# Bike_Seat_Light.net
KiCad netlist of a schematic drawn in EAGLE
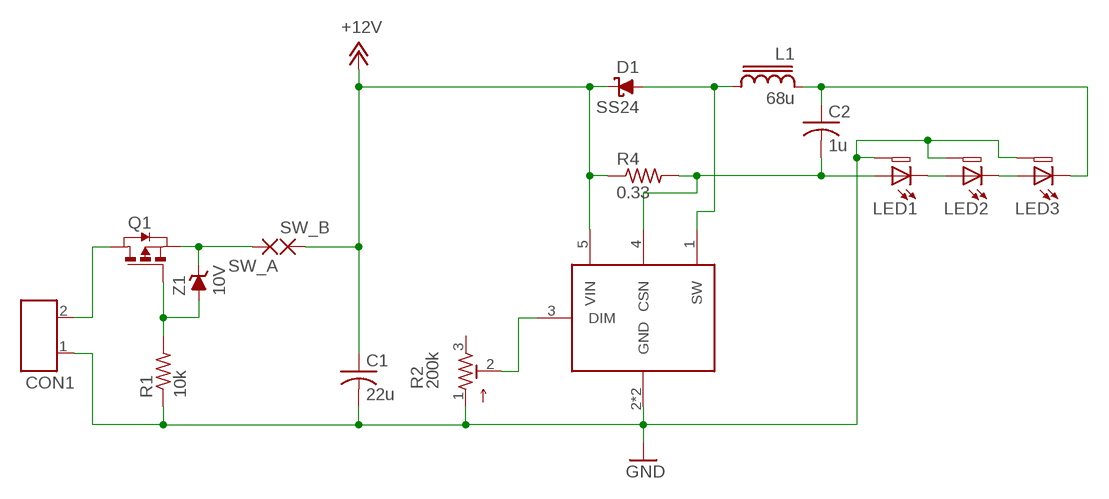
[diagram p0: schematic, sheet 1]

(export (version "E")
  (design (tool "Eeschema 10.0.6"))
  (components
    (comp (ref "C1")
      (value "22u")
      (footprint "eagle-import:C1210K")
      (libsource (lib "eagle-import") (part "C-USC1210K"))
    )
    (comp (ref "C2")
      (value "1u")
      (footprint "eagle-import:C0805K")
      (libsource (lib "eagle-import") (part "C-USC0805K"))
    )
    (comp (ref "CON1")
      (value "KF128H")
      (footprint "eagle-import:KF128H")
      (libsource (lib "eagle-import") (part "KF128H"))
    )
    (comp (ref "D1")
      (value "SS24")
      (footprint "eagle-import:DO214AC")
      (libsource (lib "eagle-import") (part "SCHOTTKYSCHOTTKY-DO214AC"))
    )
    (comp (ref "IC1")
      (value "PT4115")
      (footprint "eagle-import:SOT-89-5")
      (libsource (lib "eagle-import") (part "PT4115"))
    )
    (comp (ref "L1")
      (value "68u")
      (footprint "eagle-import:CDRH127_LD")
      (libsource (lib "eagle-import") (part "CDRH127/LD"))
    )
    (comp (ref "LED1")
      (value "POWER_LED")
      (footprint "eagle-import:POWER_LED")
      (libsource (lib "eagle-import") (part "POWER_LED"))
    )
    (comp (ref "LED2")
      (value "POWER_LED")
      (footprint "eagle-import:POWER_LED")
      (libsource (lib "eagle-import") (part "POWER_LED"))
    )
    (comp (ref "LED3")
      (value "POWER_LED")
      (footprint "eagle-import:POWER_LED")
      (libsource (lib "eagle-import") (part "POWER_LED"))
    )
    (comp (ref "Q1")
      (value "PMOSSOT23")
      (footprint "eagle-import:SOT-23")
      (libsource (lib "eagle-import") (part "PMOSSOT23"))
    )
    (comp (ref "R1")
      (value "10k")
      (footprint "eagle-import:R0805")
      (libsource (lib "eagle-import") (part "R-US_R0805"))
    )
    (comp (ref "R2")
      (value "200k")
      (footprint "eagle-import:3306F")
      (libsource (lib "eagle-import") (part "TRIM_US-3306F"))
    )
    (comp (ref "R4")
      (value "0.33")
      (footprint "eagle-import:R2512")
      (libsource (lib "eagle-import") (part "R-US_R2512"))
    )
    (comp (ref "SW_A")
      (value "1,6/0,9")
      (footprint "eagle-import:1,6_0,9")
      (libsource (lib "eagle-import") (part "1,6/0,9"))
    )
    (comp (ref "SW_B")
      (value "1,6/0,9")
      (footprint "eagle-import:1,6_0,9")
      (libsource (lib "eagle-import") (part "1,6/0,9"))
    )
    (comp (ref "Z1")
      (value "10V")
      (footprint "eagle-import:SOD123")
      (libsource (lib "eagle-import") (part "ZENER"))
    )
  )
  (nets
    (net (code "1") (name "+12V") (class "Default")
      (node (ref "C1") (pin "1") (pinfunction "1_1") (pintype "passive"))
      (node (ref "D1") (pin "C") (pinfunction "C_C") (pintype "passive"))
      (node (ref "IC1") (pin "5") (pinfunction "VIN_5") (pintype "power_in"))
      (node (ref "R4") (pin "1") (pinfunction "1_1") (pintype "passive"))
      (node (ref "SW_B") (pin "1") (pinfunction "P_1") (pintype "passive"))
    )
    (net (code "2") (name "GND") (class "Default")
      (node (ref "C1") (pin "2") (pinfunction "2_2") (pintype "passive"))
      (node (ref "CON1") (pin "1") (pinfunction "1_1") (pintype "passive"))
      (node (ref "IC1") (pin "2") (pinfunction "GND_2") (pintype "power_in"))
      (node (ref "IC1") (pin "EX") (pinfunction "GND_EX") (pintype "power_in"))
      (node (ref "LED1") (pin "T") (pinfunction "T_T") (pintype "passive"))
      (node (ref "LED2") (pin "T") (pinfunction "T_T") (pintype "passive"))
      (node (ref "LED3") (pin "T") (pinfunction "T_T") (pintype "passive"))
      (node (ref "R1") (pin "1") (pinfunction "1_1") (pintype "passive"))
      (node (ref "R2") (pin "1") (pinfunction "1_1") (pintype "passive"))
    )
    (net (code "3") (name "Net-(IC1-CSN)") (class "Default")
      (node (ref "C2") (pin "2") (pinfunction "2_2") (pintype "passive"))
      (node (ref "IC1") (pin "4") (pinfunction "CSN_4") (pintype "bidirectional"))
      (node (ref "LED1") (pin "1") (pinfunction "A_1") (pintype "passive"))
      (node (ref "R4") (pin "2") (pinfunction "2_2") (pintype "passive"))
    )
    (net (code "4") (name "Net-(IC1-DIM)") (class "Default")
      (node (ref "IC1") (pin "3") (pinfunction "DIM_3") (pintype "bidirectional"))
      (node (ref "R2") (pin "2") (pinfunction "2_2") (pintype "passive"))
    )
    (net (code "5") (name "Net-(IC1-SW)") (class "Default")
      (node (ref "D1") (pin "A") (pinfunction "A_A") (pintype "passive"))
      (node (ref "IC1") (pin "1") (pinfunction "SW_1") (pintype "bidirectional"))
      (node (ref "L1") (pin "2") (pinfunction "2_2") (pintype "passive"))
    )
    (net (code "6") (name "Net-(LED1-C)") (class "Default")
      (node (ref "LED1") (pin "2") (pinfunction "C_2") (pintype "passive"))
      (node (ref "LED2") (pin "1") (pinfunction "A_1") (pintype "passive"))
    )
    (net (code "7") (name "Net-(LED2-C)") (class "Default")
      (node (ref "LED2") (pin "2") (pinfunction "C_2") (pintype "passive"))
      (node (ref "LED3") (pin "1") (pinfunction "A_1") (pintype "passive"))
    )
    (net (code "8") (name "Net-(LED3-C)") (class "Default")
      (node (ref "C2") (pin "1") (pinfunction "1_1") (pintype "passive"))
      (node (ref "L1") (pin "1") (pinfunction "1_1") (pintype "passive"))
      (node (ref "LED3") (pin "2") (pinfunction "C_2") (pintype "passive"))
    )
    (net (code "9") (name "Net-(Q1-D)") (class "Default")
      (node (ref "CON1") (pin "2") (pinfunction "2_2") (pintype "passive"))
      (node (ref "Q1") (pin "1") (pinfunction "D_1") (pintype "passive"))
    )
    (net (code "10") (name "Net-(Q1-G)") (class "Default")
      (node (ref "Q1") (pin "3") (pinfunction "G_3") (pintype "passive"))
      (node (ref "R1") (pin "2") (pinfunction "2_2") (pintype "passive"))
      (node (ref "Z1") (pin "A") (pinfunction "A_A") (pintype "passive"))
    )
    (net (code "11") (name "Net-(Q1-S)") (class "Default")
      (node (ref "Q1") (pin "2") (pinfunction "S_2") (pintype "passive"))
      (node (ref "SW_A") (pin "1") (pinfunction "P_1") (pintype "passive"))
      (node (ref "Z1") (pin "C") (pinfunction "C_C") (pintype "passive"))
    )
    (net (code "12") (name "unconnected-(R2-Pad3)") (class "Default")
      (node (ref "R2") (pin "3") (pinfunction "3_3") (pintype "passive"))
    )
  )
)
